# Sheet1.net
KiCad netlist of a schematic drawn in Altium Designer
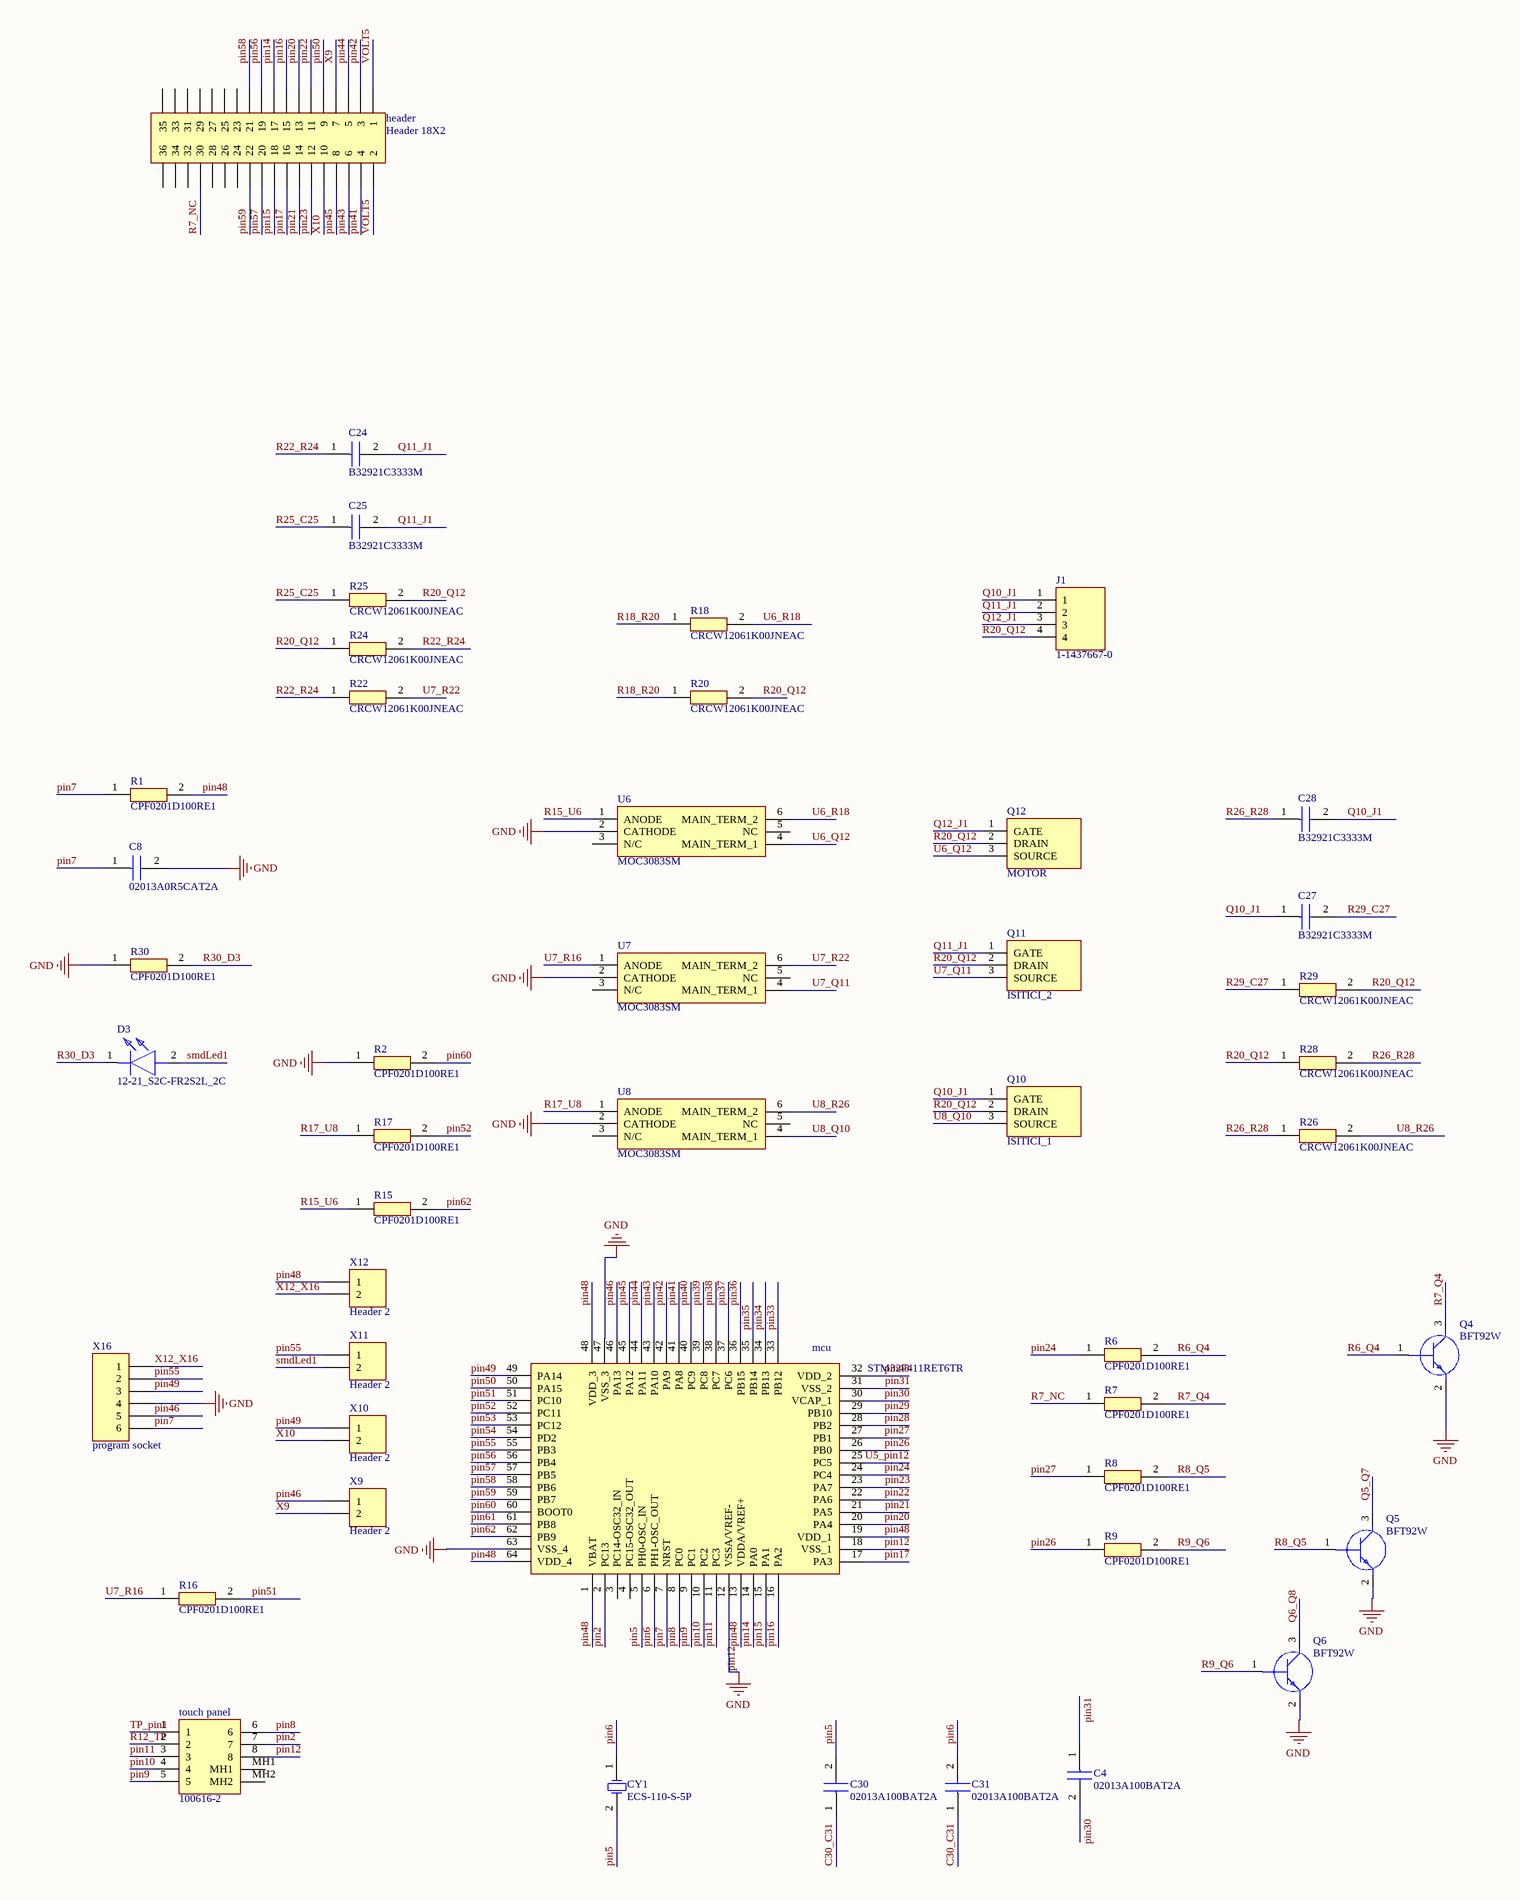
[diagram p0: Sheet1.SchDoc, left]
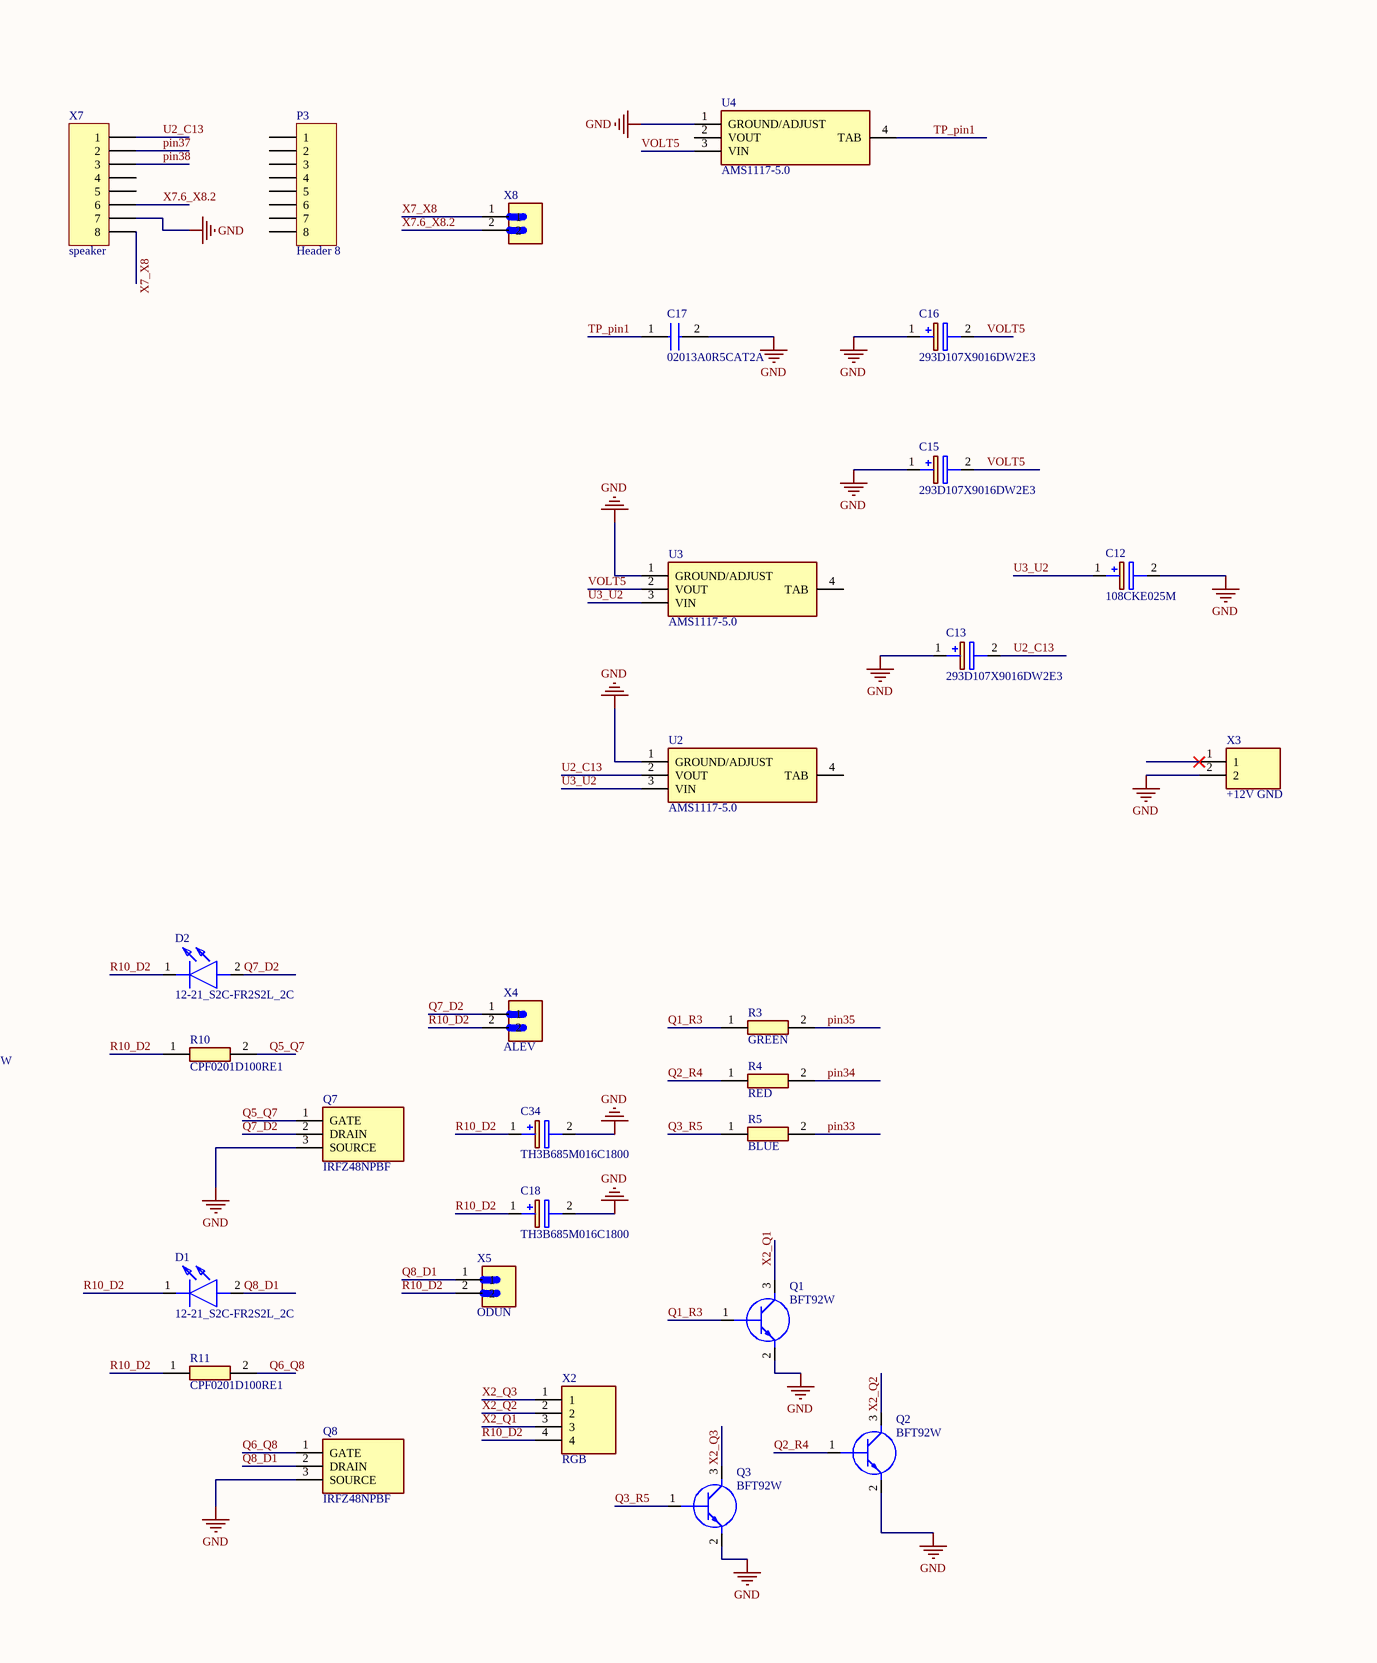
[diagram p1: Sheet1.SchDoc, middle]
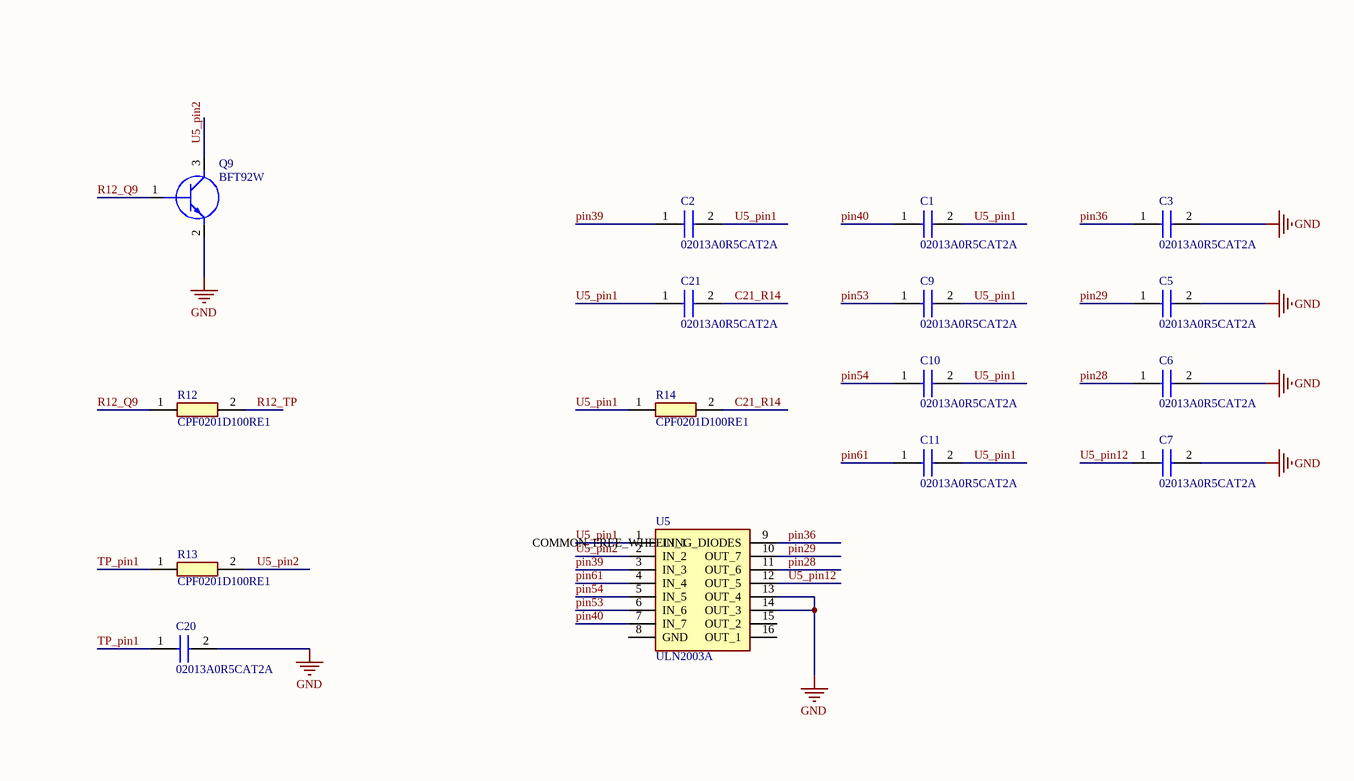
[diagram p2: Sheet1.SchDoc, right]

(export (version "E")
  (design (tool "Eeschema 10.0.6"))
  (components
    (comp (ref "C1")
      (value "02013A0R5CAT2A")
      (footprint "SamacSys:CAPC0603X33N")
      (description "Capacitor")
      (fields (field (name "MOUSER PART NUMBER") "581-02013A0R5C"))
      (libsource (lib "*") (part "02013A0R5CAT2A"))
    )
    (comp (ref "C2")
      (value "02013A0R5CAT2A")
      (footprint "SamacSys:CAPC0603X33N")
      (description "Capacitor")
      (fields (field (name "MOUSER PART NUMBER") "581-02013A0R5C"))
      (libsource (lib "*") (part "02013A0R5CAT2A"))
    )
    (comp (ref "C3")
      (value "02013A0R5CAT2A")
      (footprint "SamacSys:CAPC0603X33N")
      (description "Capacitor")
      (fields (field (name "MOUSER PART NUMBER") "581-02013A0R5C"))
      (libsource (lib "*") (part "02013A0R5CAT2A"))
    )
    (comp (ref "C4")
      (value "02013A100BAT2A")
      (footprint "SamacSys:CAPC0603X33N")
      (description "Capacitor")
      (fields (field (name "MOUSER PART NUMBER") "581-02013A100BAT2A"))
      (libsource (lib "*") (part "02013A100BAT2A"))
    )
    (comp (ref "C5")
      (value "02013A0R5CAT2A")
      (footprint "SamacSys:CAPC0603X33N")
      (description "Capacitor")
      (fields (field (name "MOUSER PART NUMBER") "581-02013A0R5C"))
      (libsource (lib "*") (part "02013A0R5CAT2A"))
    )
    (comp (ref "C6")
      (value "02013A0R5CAT2A")
      (footprint "SamacSys:CAPC0603X33N")
      (description "Capacitor")
      (fields (field (name "MOUSER PART NUMBER") "581-02013A0R5C"))
      (libsource (lib "*") (part "02013A0R5CAT2A"))
    )
    (comp (ref "C7")
      (value "02013A0R5CAT2A")
      (footprint "SamacSys:CAPC0603X33N")
      (description "Capacitor")
      (fields (field (name "MOUSER PART NUMBER") "581-02013A0R5C"))
      (libsource (lib "*") (part "02013A0R5CAT2A"))
    )
    (comp (ref "C8")
      (value "02013A0R5CAT2A")
      (footprint "SamacSys:CAPC0603X33N")
      (description "Capacitor")
      (fields (field (name "MOUSER PART NUMBER") "581-02013A0R5C"))
      (libsource (lib "*") (part "02013A0R5CAT2A"))
    )
    (comp (ref "C9")
      (value "02013A0R5CAT2A")
      (footprint "SamacSys:CAPC0603X33N")
      (description "Capacitor")
      (fields (field (name "MOUSER PART NUMBER") "581-02013A0R5C"))
      (libsource (lib "*") (part "02013A0R5CAT2A"))
    )
    (comp (ref "C10")
      (value "02013A0R5CAT2A")
      (footprint "SamacSys:CAPC0603X33N")
      (description "Capacitor")
      (fields (field (name "MOUSER PART NUMBER") "581-02013A0R5C"))
      (libsource (lib "*") (part "02013A0R5CAT2A"))
    )
    (comp (ref "C11")
      (value "02013A0R5CAT2A")
      (footprint "SamacSys:CAPC0603X33N")
      (description "Capacitor")
      (fields (field (name "MOUSER PART NUMBER") "581-02013A0R5C"))
      (libsource (lib "*") (part "02013A0R5CAT2A"))
    )
    (comp (ref "C12")
      (value "108CKE025M")
      (footprint "SamacSys:CAPPRD550W60D1050H2150")
      (description "Capacitor Polarised")
      (libsource (lib "*") (part "108CKE025M"))
    )
    (comp (ref "C13")
      (value "293D107X9016DW2E3")
      (footprint "SamacSys:CAPPM7343X310N")
      (description "Capacitor Polarised")
      (libsource (lib "*") (part "293D107X9016DW2E3"))
    )
    (comp (ref "C15")
      (value "293D107X9016DW2E3")
      (footprint "SamacSys:CAPPM7343X310N")
      (description "Capacitor Polarised")
      (libsource (lib "*") (part "293D107X9016DW2E3"))
    )
    (comp (ref "C16")
      (value "293D107X9016DW2E3")
      (footprint "SamacSys:CAPPM7343X310N")
      (description "Capacitor Polarised")
      (libsource (lib "*") (part "293D107X9016DW2E3"))
    )
    (comp (ref "C17")
      (value "02013A0R5CAT2A")
      (footprint "SamacSys:CAPC0603X33N")
      (description "Capacitor")
      (fields (field (name "MOUSER PART NUMBER") "581-02013A0R5C"))
      (libsource (lib "*") (part "02013A0R5CAT2A"))
    )
    (comp (ref "C18")
      (value "TH3B685M016C1800")
      (footprint "SamacSys:CAPPM3528X210N")
      (description "Capacitor Polarised")
      (libsource (lib "*") (part "TH3B685M016C1800"))
    )
    (comp (ref "C20")
      (value "02013A0R5CAT2A")
      (footprint "SamacSys:CAPC0603X33N")
      (description "Capacitor")
      (fields (field (name "MOUSER PART NUMBER") "581-02013A0R5C"))
      (libsource (lib "*") (part "02013A0R5CAT2A"))
    )
    (comp (ref "C21")
      (value "02013A0R5CAT2A")
      (footprint "SamacSys:CAPC0603X33N")
      (description "Capacitor")
      (fields (field (name "MOUSER PART NUMBER") "581-02013A0R5C"))
      (libsource (lib "*") (part "02013A0R5CAT2A"))
    )
    (comp (ref "C24")
      (value "B32921C3333M")
      (footprint "SamacSys:B32921C3333M")
      (description "Capacitor")
      (fields (field (name "MOUSER PART NUMBER") "871-B32921C3333M"))
      (libsource (lib "*") (part "B32921C3333M"))
    )
    (comp (ref "C25")
      (value "B32921C3333M")
      (footprint "SamacSys:B32921C3333M")
      (description "Capacitor")
      (fields (field (name "MOUSER PART NUMBER") "871-B32921C3333M"))
      (libsource (lib "*") (part "B32921C3333M"))
    )
    (comp (ref "C27")
      (value "B32921C3333M")
      (footprint "SamacSys:B32921C3333M")
      (description "Capacitor")
      (fields (field (name "MOUSER PART NUMBER") "871-B32921C3333M"))
      (libsource (lib "*") (part "B32921C3333M"))
    )
    (comp (ref "C28")
      (value "B32921C3333M")
      (footprint "SamacSys:B32921C3333M")
      (description "Capacitor")
      (fields (field (name "MOUSER PART NUMBER") "871-B32921C3333M"))
      (libsource (lib "*") (part "B32921C3333M"))
    )
    (comp (ref "C30")
      (value "02013A100BAT2A")
      (footprint "SamacSys:CAPC0603X33N")
      (description "Capacitor")
      (fields (field (name "MOUSER PART NUMBER") "581-02013A100BAT2A"))
      (libsource (lib "*") (part "02013A100BAT2A"))
    )
    (comp (ref "C31")
      (value "02013A100BAT2A")
      (footprint "SamacSys:CAPC0603X33N")
      (description "Capacitor")
      (fields (field (name "MOUSER PART NUMBER") "581-02013A100BAT2A"))
      (libsource (lib "*") (part "02013A100BAT2A"))
    )
    (comp (ref "C34")
      (value "TH3B685M016C1800")
      (footprint "SamacSys:CAPPM3528X210N")
      (description "Capacitor Polarised")
      (libsource (lib "*") (part "TH3B685M016C1800"))
    )
    (comp (ref "CY1")
      (value "ECS-110-S-5P")
      (footprint "CSM-7")
      (description "Crystal Oscillator")
      (fields (field (name "PUBLISHER") "Altium Limited"))
      (libsource (lib "ECS Crystal Oscillator") (part "ECS-110-S-5P"))
    )
    (comp (ref "D1")
      (value "12-21_S2C-FR2S2L_2C")
      (footprint "SamacSys:1221S2CFR2S2L2C")
      (description "LED")
      (fields (field (name "MANUFACTURER_PART_NUMBER") "12-21/S2C-FR2S2L/2C"))
      (libsource (lib "SamacSys") (part "12-21_S2C-FR2S2L_2C"))
    )
    (comp (ref "D2")
      (value "12-21_S2C-FR2S2L_2C")
      (footprint "SamacSys:1221S2CFR2S2L2C")
      (description "LED")
      (fields (field (name "MANUFACTURER_PART_NUMBER") "12-21/S2C-FR2S2L/2C"))
      (libsource (lib "SamacSys") (part "12-21_S2C-FR2S2L_2C"))
    )
    (comp (ref "D3")
      (value "12-21_S2C-FR2S2L_2C")
      (footprint "SamacSys:1221S2CFR2S2L2C")
      (description "LED")
      (fields (field (name "MANUFACTURER_PART_NUMBER") "12-21/S2C-FR2S2L/2C"))
      (libsource (lib "*") (part "12-21_S2C-FR2S2L_2C"))
    )
    (comp (ref "header")
      (value "Header 18X2")
      (footprint "HDR2X18")
      (description "Header, 18-Pin, Dual row")
      (fields (field (name "PUBLISHER") "Altium Limited"))
      (libsource (lib "Miscellaneous Connectors") (part "Header 18X2"))
    )
    (comp (ref "J1")
      (value "1-1437667-0")
      (footprint "SamacSys:114376670")
      (description "Connector")
      (libsource (lib "*") (part "1-1437667-0"))
    )
    (comp (ref "mcu")
      (value "STM32F411RET6TR")
      (footprint "SamacSys:QFP50P1200X1200X160-64N")
      (description "Integrated Circuit")
      (fields (field (name "MOUSER PART NUMBER") "511-STM32F411RET6TR"))
      (libsource (lib "*") (part "STM32F411RET6TR"))
    )
    (comp (ref "P3")
      (value "Header 8")
      (footprint "HDR1X8")
      (description "Header, 8-Pin")
      (fields (field (name "PUBLISHER") "Altium Limited"))
      (libsource (lib "") (part "Header 8_1"))
    )
    (comp (ref "Q1")
      (value "BFT92W")
      (footprint "SamacSys:SOT65P210X110-3N")
      (description "Transistor BJT NPN")
      (libsource (lib "*") (part "BFT92W"))
    )
    (comp (ref "Q2")
      (value "BFT92W")
      (footprint "SamacSys:SOT65P210X110-3N")
      (description "Transistor BJT NPN")
      (libsource (lib "*") (part "BFT92W"))
    )
    (comp (ref "Q3")
      (value "BFT92W")
      (footprint "SamacSys:SOT65P210X110-3N")
      (description "Transistor BJT NPN")
      (libsource (lib "*") (part "BFT92W"))
    )
    (comp (ref "Q4")
      (value "BFT92W")
      (footprint "SamacSys:SOT65P210X110-3N")
      (description "Transistor BJT NPN")
      (libsource (lib "*") (part "BFT92W"))
    )
    (comp (ref "Q5")
      (value "BFT92W")
      (footprint "SamacSys:SOT65P210X110-3N")
      (description "Transistor BJT NPN")
      (libsource (lib "*") (part "BFT92W"))
    )
    (comp (ref "Q6")
      (value "BFT92W")
      (footprint "SamacSys:SOT65P210X110-3N")
      (description "Transistor BJT NPN")
      (libsource (lib "*") (part "BFT92W"))
    )
    (comp (ref "Q7")
      (value "IRFZ48NPBF")
      (footprint "SamacSys:TO254P483X1016X1994-3P")
      (description "Transistor")
      (fields (field (name "MOUSER PART NUMBER") "942-IRFZ48NPBF"))
      (libsource (lib "SamacSys") (part "IRFZ48NPBF"))
    )
    (comp (ref "Q8")
      (value "IRFZ48NPBF")
      (footprint "SamacSys:TO254P483X1016X1994-3P")
      (description "Transistor")
      (fields (field (name "MOUSER PART NUMBER") "942-IRFZ48NPBF"))
      (libsource (lib "SamacSys") (part "IRFZ48NPBF"))
    )
    (comp (ref "Q9")
      (value "BFT92W")
      (footprint "SamacSys:SOT65P210X110-3N")
      (description "Transistor BJT NPN")
      (libsource (lib "*") (part "BFT92W"))
    )
    (comp (ref "Q10")
      (value "ISITICI_1")
      (footprint "SamacSys:TO254P483X1016X1994-3P")
      (description "Transistor")
      (fields
        (field (name "MANUFACTURER_PART_NUMBER") "IRFZ48NPBF")
        (field (name "MOUSER PART NUMBER") "942-IRFZ48NPBF")
      )
      (libsource (lib "SamacSys") (part "IRFZ48NPBF"))
    )
    (comp (ref "Q11")
      (value "ISITICI_2")
      (footprint "SamacSys:TO254P483X1016X1994-3P")
      (description "Transistor")
      (fields
        (field (name "MANUFACTURER_PART_NUMBER") "IRFZ48NPBF")
        (field (name "MOUSER PART NUMBER") "942-IRFZ48NPBF")
      )
      (libsource (lib "SamacSys") (part "IRFZ48NPBF"))
    )
    (comp (ref "Q12")
      (value "MOTOR")
      (footprint "SamacSys:TO254P483X1016X1994-3P")
      (description "Transistor")
      (fields
        (field (name "MANUFACTURER_PART_NUMBER") "IRFZ48NPBF")
        (field (name "MOUSER PART NUMBER") "942-IRFZ48NPBF")
      )
      (libsource (lib "SamacSys") (part "IRFZ48NPBF"))
    )
    (comp (ref "R1")
      (value "CPF0201D100RE1")
      (footprint "SamacSys:RESC0603X28N")
      (description "Resistor")
      (fields (field (name "MOUSER PART NUMBER") "279-CPF0201D100RE1"))
      (libsource (lib "*") (part "CPF0201D100RE1"))
    )
    (comp (ref "R2")
      (value "CPF0201D100RE1")
      (footprint "SamacSys:RESC0603X28N")
      (description "Resistor")
      (fields (field (name "MOUSER PART NUMBER") "279-CPF0201D100RE1"))
      (libsource (lib "*") (part "CPF0201D100RE1"))
    )
    (comp (ref "R3")
      (value "GREEN")
      (footprint "SamacSys:RESC0603X28N")
      (description "Resistor")
      (fields
        (field (name "MANUFACTURER_PART_NUMBER") "CPF0201D100RE1")
        (field (name "MOUSER PART NUMBER") "279-CPF0201D100RE1")
      )
      (libsource (lib "*") (part "CPF0201D100RE1"))
    )
    (comp (ref "R4")
      (value "RED")
      (footprint "SamacSys:RESC0603X28N")
      (description "Resistor")
      (fields
        (field (name "MANUFACTURER_PART_NUMBER") "CPF0201D100RE1")
        (field (name "MOUSER PART NUMBER") "279-CPF0201D100RE1")
      )
      (libsource (lib "*") (part "CPF0201D100RE1"))
    )
    (comp (ref "R5")
      (value "BLUE")
      (footprint "SamacSys:RESC0603X28N")
      (description "Resistor")
      (fields
        (field (name "MANUFACTURER_PART_NUMBER") "CPF0201D100RE1")
        (field (name "MOUSER PART NUMBER") "279-CPF0201D100RE1")
      )
      (libsource (lib "*") (part "CPF0201D100RE1"))
    )
    (comp (ref "R6")
      (value "CPF0201D100RE1")
      (footprint "SamacSys:RESC0603X28N")
      (description "Resistor")
      (fields (field (name "MOUSER PART NUMBER") "279-CPF0201D100RE1"))
      (libsource (lib "*") (part "CPF0201D100RE1"))
    )
    (comp (ref "R7")
      (value "CPF0201D100RE1")
      (footprint "SamacSys:RESC0603X28N")
      (description "Resistor")
      (fields (field (name "MOUSER PART NUMBER") "279-CPF0201D100RE1"))
      (libsource (lib "*") (part "CPF0201D100RE1"))
    )
    (comp (ref "R8")
      (value "CPF0201D100RE1")
      (footprint "SamacSys:RESC0603X28N")
      (description "Resistor")
      (fields (field (name "MOUSER PART NUMBER") "279-CPF0201D100RE1"))
      (libsource (lib "*") (part "CPF0201D100RE1"))
    )
    (comp (ref "R9")
      (value "CPF0201D100RE1")
      (footprint "SamacSys:RESC0603X28N")
      (description "Resistor")
      (fields (field (name "MOUSER PART NUMBER") "279-CPF0201D100RE1"))
      (libsource (lib "*") (part "CPF0201D100RE1"))
    )
    (comp (ref "R10")
      (value "CPF0201D100RE1")
      (footprint "SamacSys:RESC0603X28N")
      (description "Resistor")
      (fields (field (name "MOUSER PART NUMBER") "279-CPF0201D100RE1"))
      (libsource (lib "*") (part "CPF0201D100RE1"))
    )
    (comp (ref "R11")
      (value "CPF0201D100RE1")
      (footprint "SamacSys:RESC0603X28N")
      (description "Resistor")
      (fields (field (name "MOUSER PART NUMBER") "279-CPF0201D100RE1"))
      (libsource (lib "*") (part "CPF0201D100RE1"))
    )
    (comp (ref "R12")
      (value "CPF0201D100RE1")
      (footprint "SamacSys:RESC0603X28N")
      (description "Resistor")
      (fields (field (name "MOUSER PART NUMBER") "279-CPF0201D100RE1"))
      (libsource (lib "*") (part "CPF0201D100RE1"))
    )
    (comp (ref "R13")
      (value "CPF0201D100RE1")
      (footprint "SamacSys:RESC0603X28N")
      (description "Resistor")
      (fields (field (name "MOUSER PART NUMBER") "279-CPF0201D100RE1"))
      (libsource (lib "*") (part "CPF0201D100RE1"))
    )
    (comp (ref "R14")
      (value "CPF0201D100RE1")
      (footprint "SamacSys:RESC0603X28N")
      (description "Resistor")
      (fields (field (name "MOUSER PART NUMBER") "279-CPF0201D100RE1"))
      (libsource (lib "*") (part "CPF0201D100RE1"))
    )
    (comp (ref "R15")
      (value "CPF0201D100RE1")
      (footprint "SamacSys:RESC0603X28N")
      (description "Resistor")
      (fields (field (name "MOUSER PART NUMBER") "279-CPF0201D100RE1"))
      (libsource (lib "*") (part "CPF0201D100RE1"))
    )
    (comp (ref "R16")
      (value "CPF0201D100RE1")
      (footprint "SamacSys:RESC0603X28N")
      (description "Resistor")
      (fields (field (name "MOUSER PART NUMBER") "279-CPF0201D100RE1"))
      (libsource (lib "*") (part "CPF0201D100RE1"))
    )
    (comp (ref "R17")
      (value "CPF0201D100RE1")
      (footprint "SamacSys:RESC0603X28N")
      (description "Resistor")
      (fields (field (name "MOUSER PART NUMBER") "279-CPF0201D100RE1"))
      (libsource (lib "*") (part "CPF0201D100RE1"))
    )
    (comp (ref "R18")
      (value "CRCW12061K00JNEAC")
      (footprint "SamacSys:RESC3216X60N")
      (description "Resistor")
      (fields (field (name "MOUSER PART NUMBER") "71-CRCW12061K00JNEAC"))
      (libsource (lib "*") (part "CRCW12061K00JNEAC"))
    )
    (comp (ref "R20")
      (value "CRCW12061K00JNEAC")
      (footprint "SamacSys:RESC3216X60N")
      (description "Resistor")
      (fields (field (name "MOUSER PART NUMBER") "71-CRCW12061K00JNEAC"))
      (libsource (lib "*") (part "CRCW12061K00JNEAC"))
    )
    (comp (ref "R22")
      (value "CRCW12061K00JNEAC")
      (footprint "SamacSys:RESC3216X60N")
      (description "Resistor")
      (fields (field (name "MOUSER PART NUMBER") "71-CRCW12061K00JNEAC"))
      (libsource (lib "*") (part "CRCW12061K00JNEAC"))
    )
    (comp (ref "R24")
      (value "CRCW12061K00JNEAC")
      (footprint "SamacSys:RESC3216X60N")
      (description "Resistor")
      (fields (field (name "MOUSER PART NUMBER") "71-CRCW12061K00JNEAC"))
      (libsource (lib "*") (part "CRCW12061K00JNEAC"))
    )
    (comp (ref "R25")
      (value "CRCW12061K00JNEAC")
      (footprint "SamacSys:RESC3216X60N")
      (description "Resistor")
      (fields (field (name "MOUSER PART NUMBER") "71-CRCW12061K00JNEAC"))
      (libsource (lib "*") (part "CRCW12061K00JNEAC"))
    )
    (comp (ref "R26")
      (value "CRCW12061K00JNEAC")
      (footprint "SamacSys:RESC3216X60N")
      (description "Resistor")
      (fields (field (name "MOUSER PART NUMBER") "71-CRCW12061K00JNEAC"))
      (libsource (lib "*") (part "CRCW12061K00JNEAC"))
    )
    (comp (ref "R28")
      (value "CRCW12061K00JNEAC")
      (footprint "SamacSys:RESC3216X60N")
      (description "Resistor")
      (fields (field (name "MOUSER PART NUMBER") "71-CRCW12061K00JNEAC"))
      (libsource (lib "*") (part "CRCW12061K00JNEAC"))
    )
    (comp (ref "R29")
      (value "CRCW12061K00JNEAC")
      (footprint "SamacSys:RESC3216X60N")
      (description "Resistor")
      (fields (field (name "MOUSER PART NUMBER") "71-CRCW12061K00JNEAC"))
      (libsource (lib "*") (part "CRCW12061K00JNEAC"))
    )
    (comp (ref "R30")
      (value "CPF0201D100RE1")
      (footprint "SamacSys:RESC0603X28N")
      (description "Resistor")
      (fields (field (name "MOUSER PART NUMBER") "279-CPF0201D100RE1"))
      (libsource (lib "*") (part "CPF0201D100RE1"))
    )
    (comp (ref "touch panel")
      (value "100616-2")
      (footprint "SamacSys:1006162")
      (description "Connector")
      (fields (field (name "MOUSER PART NUMBER") "571-100616-2"))
      (libsource (lib "SamacSys") (part "100616-2"))
    )
    (comp (ref "U2")
      (value "AMS1117-5.0")
      (footprint "SamacSys:SOT229P700X180-4N")
      (description "Integrated Circuit")
      (libsource (lib "*") (part "AMS1117-5.0"))
    )
    (comp (ref "U3")
      (value "AMS1117-5.0")
      (footprint "SamacSys:SOT229P700X180-4N")
      (description "Integrated Circuit")
      (libsource (lib "*") (part "AMS1117-5.0"))
    )
    (comp (ref "U4")
      (value "AMS1117-5.0")
      (footprint "SamacSys:SOT229P700X180-4N")
      (description "Integrated Circuit")
      (libsource (lib "*") (part "AMS1117-5.0"))
    )
    (comp (ref "U5")
      (value "ULN2003A")
      (footprint "SamacSys:DIP794W56P254L1888H533Q16N")
      (description "Integrated Circuit")
      (fields (field (name "MOUSER PART NUMBER") "511-ULN2003A"))
      (libsource (lib "*") (part "ULN2003A"))
    )
    (comp (ref "U6")
      (value "MOC3083SM")
      (footprint "SamacSys:DIP762W51P254L851H508Q6N")
      (description "Integrated Circuit")
      (fields (field (name "MOUSER PART NUMBER") "512-MOC3083SM"))
      (libsource (lib "*") (part "MOC3083SM"))
    )
    (comp (ref "U7")
      (value "MOC3083SM")
      (footprint "SamacSys:DIP762W51P254L851H508Q6N")
      (description "Integrated Circuit")
      (fields (field (name "MOUSER PART NUMBER") "512-MOC3083SM"))
      (libsource (lib "*") (part "MOC3083SM"))
    )
    (comp (ref "U8")
      (value "MOC3083SM")
      (footprint "SamacSys:DIP762W51P254L851H508Q6N")
      (description "Integrated Circuit")
      (fields (field (name "MOUSER PART NUMBER") "512-MOC3083SM"))
      (libsource (lib "*") (part "MOC3083SM"))
    )
    (comp (ref "X2")
      (value "RGB")
      (footprint "SamacSys:1844236")
      (description "Connector")
      (fields
        (field (name "MANUFACTURER_PART_NUMBER") "1844236")
        (field (name "MOUSER PART NUMBER") "651-1844236")
      )
      (libsource (lib "*") (part "1844236"))
    )
    (comp (ref "X3")
      (value "+12V GND")
      (footprint "SamacSys:SHDR2W100P0X508_1X2_1020X780X1200P")
      (description "Connector")
      (fields (field (name "MANUFACTURER_PART_NUMBER") "CTBP9308/2AO"))
      (libsource (lib "*") (part "CTBP9308_2AO"))
    )
    (comp (ref "X4")
      (value "ALEV")
      (footprint "PHOENIX_1803277")
      (fields
        (field (name "DIGI-KEY_PART_NUMBER") "277-1206-ND")
        (field (name "MP") "1803277")
        (field (name "MF") "Phoenix Contact")
      )
      (libsource (lib "1803277") (part "1803277"))
    )
    (comp (ref "X5")
      (value "ODUN")
      (footprint "PHOENIX_1803277")
      (fields
        (field (name "DIGI-KEY_PART_NUMBER") "277-1206-ND")
        (field (name "MP") "1803277")
        (field (name "MF") "Phoenix Contact")
      )
      (libsource (lib "1803277") (part "1803277"))
    )
    (comp (ref "X7")
      (value "speaker")
      (footprint "HDR1X8")
      (description "Header, 8-Pin")
      (fields (field (name "PUBLISHER") "Altium Limited"))
      (libsource (lib "Miscellaneous Connectors") (part "Header 8"))
    )
    (comp (ref "X8")
      (value "~")
      (footprint "PHOENIX_1803277")
      (fields
        (field (name "DIGI-KEY_PART_NUMBER") "277-1206-ND")
        (field (name "MP") "1803277")
        (field (name "MF") "Phoenix Contact")
      )
      (libsource (lib "1803277") (part "1803277"))
    )
    (comp (ref "X9")
      (value "Header 2")
      (footprint "HDR1X2")
      (description "Header, 2-Pin")
      (fields (field (name "PUBLISHER") "Altium Limited"))
      (libsource (lib "Miscellaneous Connectors") (part "Header 2"))
    )
    (comp (ref "X10")
      (value "Header 2")
      (footprint "HDR1X2")
      (description "Header, 2-Pin")
      (fields (field (name "PUBLISHER") "Altium Limited"))
      (libsource (lib "Miscellaneous Connectors") (part "Header 2"))
    )
    (comp (ref "X11")
      (value "Header 2")
      (footprint "HDR1X2")
      (description "Header, 2-Pin")
      (fields (field (name "PUBLISHER") "Altium Limited"))
      (libsource (lib "Miscellaneous Connectors") (part "Header 2"))
    )
    (comp (ref "X12")
      (value "Header 2")
      (footprint "HDR1X2")
      (description "Header, 2-Pin")
      (fields (field (name "PUBLISHER") "Altium Limited"))
      (libsource (lib "Miscellaneous Connectors") (part "Header 2"))
    )
    (comp (ref "X16")
      (value "program socket")
      (footprint "HDR1X6")
      (description "Header, 6-Pin")
      (fields (field (name "PUBLISHER") "Altium Limited"))
      (libsource (lib "Miscellaneous Connectors") (part "Header 6"))
    )
  )
  (nets
    (net (code "1") (name "/C21_R14") (class "Default")
      (node (ref "C21") (pin "2") (pinfunction "2_2") (pintype "passive"))
      (node (ref "R14") (pin "2") (pinfunction "2_2") (pintype "passive"))
    )
    (net (code "2") (name "/C30_C31") (class "Default")
      (node (ref "C30") (pin "1") (pinfunction "1_1") (pintype "passive"))
      (node (ref "C31") (pin "1") (pinfunction "1_1") (pintype "passive"))
    )
    (net (code "3") (name "/Q1_R3") (class "Default")
      (node (ref "Q1") (pin "1") (pinfunction "B_1") (pintype "passive"))
      (node (ref "R3") (pin "1") (pinfunction "1_1") (pintype "passive"))
    )
    (net (code "4") (name "/Q2_R4") (class "Default")
      (node (ref "Q2") (pin "1") (pinfunction "B_1") (pintype "passive"))
      (node (ref "R4") (pin "1") (pinfunction "1_1") (pintype "passive"))
    )
    (net (code "5") (name "/Q3_R5") (class "Default")
      (node (ref "Q3") (pin "1") (pinfunction "B_1") (pintype "passive"))
      (node (ref "R5") (pin "1") (pinfunction "1_1") (pintype "passive"))
    )
    (net (code "6") (name "/Q5_Q7") (class "Default")
      (node (ref "Q5") (pin "3") (pinfunction "C_3") (pintype "passive"))
      (node (ref "Q7") (pin "1") (pinfunction "GATE_1") (pintype "passive"))
      (node (ref "R10") (pin "2") (pinfunction "2_2") (pintype "passive"))
    )
    (net (code "7") (name "/Q6_Q8") (class "Default")
      (node (ref "Q6") (pin "3") (pinfunction "C_3") (pintype "passive"))
      (node (ref "Q8") (pin "1") (pinfunction "GATE_1") (pintype "passive"))
      (node (ref "R11") (pin "2") (pinfunction "2_2") (pintype "passive"))
    )
    (net (code "8") (name "/Q7_D2") (class "Default")
      (node (ref "D2") (pin "2") (pinfunction "A_2") (pintype "passive"))
      (node (ref "Q7") (pin "2") (pinfunction "DRAIN_2") (pintype "passive"))
      (node (ref "X4") (pin "1") (pinfunction "1_1") (pintype "passive"))
    )
    (net (code "9") (name "/Q8_D1") (class "Default")
      (node (ref "D1") (pin "2") (pinfunction "A_2") (pintype "passive"))
      (node (ref "Q8") (pin "2") (pinfunction "DRAIN_2") (pintype "passive"))
      (node (ref "X5") (pin "1") (pinfunction "1_1") (pintype "passive"))
    )
    (net (code "10") (name "/Q10_J1") (class "Default")
      (node (ref "C27") (pin "1") (pinfunction "1_1") (pintype "passive"))
      (node (ref "C28") (pin "2") (pinfunction "2_2") (pintype "passive"))
      (node (ref "J1") (pin "1") (pinfunction "1_1") (pintype "passive"))
      (node (ref "Q10") (pin "1") (pinfunction "GATE_1") (pintype "passive"))
    )
    (net (code "11") (name "/Q11_J1") (class "Default")
      (node (ref "C24") (pin "2") (pinfunction "2_2") (pintype "passive"))
      (node (ref "C25") (pin "2") (pinfunction "2_2") (pintype "passive"))
      (node (ref "J1") (pin "2") (pinfunction "2_2") (pintype "passive"))
      (node (ref "Q11") (pin "1") (pinfunction "GATE_1") (pintype "passive"))
    )
    (net (code "12") (name "/Q12_J1") (class "Default")
      (node (ref "J1") (pin "3") (pinfunction "3_3") (pintype "passive"))
      (node (ref "Q12") (pin "1") (pinfunction "GATE_1") (pintype "passive"))
    )
    (net (code "13") (name "/R6_Q4") (class "Default")
      (node (ref "Q4") (pin "1") (pinfunction "B_1") (pintype "passive"))
      (node (ref "R6") (pin "2") (pinfunction "2_2") (pintype "passive"))
    )
    (net (code "14") (name "/R7_NC") (class "Default")
      (node (ref "R7") (pin "1") (pinfunction "1_1") (pintype "passive"))
      (node (ref "header") (pin "30") (pinfunction "30_30") (pintype "passive"))
    )
    (net (code "15") (name "/R7_Q4") (class "Default")
      (node (ref "Q4") (pin "3") (pinfunction "C_3") (pintype "passive"))
      (node (ref "R7") (pin "2") (pinfunction "2_2") (pintype "passive"))
    )
    (net (code "16") (name "/R8_Q5") (class "Default")
      (node (ref "Q5") (pin "1") (pinfunction "B_1") (pintype "passive"))
      (node (ref "R8") (pin "2") (pinfunction "2_2") (pintype "passive"))
    )
    (net (code "17") (name "/R9_Q6") (class "Default")
      (node (ref "Q6") (pin "1") (pinfunction "B_1") (pintype "passive"))
      (node (ref "R9") (pin "2") (pinfunction "2_2") (pintype "passive"))
    )
    (net (code "18") (name "/R10_D2") (class "Default")
      (node (ref "C18") (pin "1") (pinfunction "+_1") (pintype "passive"))
      (node (ref "C34") (pin "1") (pinfunction "+_1") (pintype "passive"))
      (node (ref "D1") (pin "1") (pinfunction "K_1") (pintype "passive"))
      (node (ref "D2") (pin "1") (pinfunction "K_1") (pintype "passive"))
      (node (ref "R10") (pin "1") (pinfunction "1_1") (pintype "passive"))
      (node (ref "R11") (pin "1") (pinfunction "1_1") (pintype "passive"))
      (node (ref "X2") (pin "4") (pinfunction "4_4") (pintype "passive"))
      (node (ref "X4") (pin "2") (pinfunction "2_2") (pintype "passive"))
      (node (ref "X5") (pin "2") (pinfunction "2_2") (pintype "passive"))
    )
    (net (code "19") (name "/R12_Q9") (class "Default")
      (node (ref "Q9") (pin "1") (pinfunction "B_1") (pintype "passive"))
      (node (ref "R12") (pin "1") (pinfunction "1_1") (pintype "passive"))
    )
    (net (code "20") (name "/R12_TP") (class "Default")
      (node (ref "R12") (pin "2") (pinfunction "2_2") (pintype "passive"))
      (node (ref "touch panel") (pin "2") (pinfunction "2_2") (pintype "passive"))
    )
    (net (code "21") (name "/R15_U6") (class "Default")
      (node (ref "R15") (pin "1") (pinfunction "1_1") (pintype "passive"))
      (node (ref "U6") (pin "1") (pinfunction "ANODE_1") (pintype "passive"))
    )
    (net (code "22") (name "/R17_U8") (class "Default")
      (node (ref "R17") (pin "1") (pinfunction "1_1") (pintype "passive"))
      (node (ref "U8") (pin "1") (pinfunction "ANODE_1") (pintype "passive"))
    )
    (net (code "23") (name "/R18_R20") (class "Default")
      (node (ref "R18") (pin "1") (pinfunction "1_1") (pintype "passive"))
      (node (ref "R20") (pin "1") (pinfunction "1_1") (pintype "passive"))
    )
    (net (code "24") (name "/R20_Q12") (class "Default")
      (node (ref "J1") (pin "4") (pinfunction "4_4") (pintype "passive"))
      (node (ref "Q10") (pin "2") (pinfunction "DRAIN_2") (pintype "passive"))
      (node (ref "Q11") (pin "2") (pinfunction "DRAIN_2") (pintype "passive"))
      (node (ref "Q12") (pin "2") (pinfunction "DRAIN_2") (pintype "passive"))
      (node (ref "R20") (pin "2") (pinfunction "2_2") (pintype "passive"))
      (node (ref "R24") (pin "1") (pinfunction "1_1") (pintype "passive"))
      (node (ref "R25") (pin "2") (pinfunction "2_2") (pintype "passive"))
      (node (ref "R28") (pin "1") (pinfunction "1_1") (pintype "passive"))
      (node (ref "R29") (pin "2") (pinfunction "2_2") (pintype "passive"))
    )
    (net (code "25") (name "/R22_R24") (class "Default")
      (node (ref "C24") (pin "1") (pinfunction "1_1") (pintype "passive"))
      (node (ref "R22") (pin "1") (pinfunction "1_1") (pintype "passive"))
      (node (ref "R24") (pin "2") (pinfunction "2_2") (pintype "passive"))
    )
    (net (code "26") (name "/R25_C25") (class "Default")
      (node (ref "C25") (pin "1") (pinfunction "1_1") (pintype "passive"))
      (node (ref "R25") (pin "1") (pinfunction "1_1") (pintype "passive"))
    )
    (net (code "27") (name "/R26_R28") (class "Default")
      (node (ref "C28") (pin "1") (pinfunction "1_1") (pintype "passive"))
      (node (ref "R26") (pin "1") (pinfunction "1_1") (pintype "passive"))
      (node (ref "R28") (pin "2") (pinfunction "2_2") (pintype "passive"))
    )
    (net (code "28") (name "/R29_C27") (class "Default")
      (node (ref "C27") (pin "2") (pinfunction "2_2") (pintype "passive"))
      (node (ref "R29") (pin "1") (pinfunction "1_1") (pintype "passive"))
    )
    (net (code "29") (name "/R30_D3") (class "Default")
      (node (ref "D3") (pin "1") (pinfunction "K_1") (pintype "passive"))
      (node (ref "R30") (pin "2") (pinfunction "2_2") (pintype "passive"))
    )
    (net (code "30") (name "/TP_pin1") (class "Default")
      (node (ref "C17") (pin "1") (pinfunction "1_1") (pintype "passive"))
      (node (ref "C20") (pin "1") (pinfunction "1_1") (pintype "passive"))
      (node (ref "R13") (pin "1") (pinfunction "1_1") (pintype "passive"))
      (node (ref "U4") (pin "4") (pinfunction "TAB_4") (pintype "passive"))
      (node (ref "touch panel") (pin "1") (pinfunction "1_1") (pintype "passive"))
    )
    (net (code "31") (name "/U2_C13") (class "Default")
      (node (ref "C13") (pin "2") (pinfunction "-_2") (pintype "passive"))
      (node (ref "U2") (pin "2") (pinfunction "VOUT_2") (pintype "passive"))
      (node (ref "X7") (pin "1") (pinfunction "1_1") (pintype "passive"))
    )
    (net (code "32") (name "/U3_U2") (class "Default")
      (node (ref "C12") (pin "1") (pinfunction "+_1") (pintype "passive"))
      (node (ref "U2") (pin "3") (pinfunction "VIN_3") (pintype "passive"))
      (node (ref "U3") (pin "3") (pinfunction "VIN_3") (pintype "passive"))
    )
    (net (code "33") (name "/U5_pin1") (class "Default")
      (node (ref "C1") (pin "2") (pinfunction "2_2") (pintype "passive"))
      (node (ref "C10") (pin "2") (pinfunction "2_2") (pintype "passive"))
      (node (ref "C11") (pin "2") (pinfunction "2_2") (pintype "passive"))
      (node (ref "C2") (pin "2") (pinfunction "2_2") (pintype "passive"))
      (node (ref "C21") (pin "1") (pinfunction "1_1") (pintype "passive"))
      (node (ref "C9") (pin "2") (pinfunction "2_2") (pintype "passive"))
      (node (ref "R14") (pin "1") (pinfunction "1_1") (pintype "passive"))
      (node (ref "U5") (pin "1") (pinfunction "IN_1_1") (pintype "passive"))
    )
    (net (code "34") (name "/U5_pin2") (class "Default")
      (node (ref "Q9") (pin "3") (pinfunction "C_3") (pintype "passive"))
      (node (ref "R13") (pin "2") (pinfunction "2_2") (pintype "passive"))
      (node (ref "U5") (pin "2") (pinfunction "IN_2_2") (pintype "passive"))
    )
    (net (code "35") (name "/U5_pin12") (class "Default")
      (node (ref "C7") (pin "1") (pinfunction "1_1") (pintype "passive"))
      (node (ref "U5") (pin "12") (pinfunction "OUT_5_12") (pintype "passive"))
      (node (ref "mcu") (pin "25") (pinfunction "PC5_25") (pintype "passive"))
    )
    (net (code "36") (name "/U6_Q12") (class "Default")
      (node (ref "Q12") (pin "3") (pinfunction "SOURCE_3") (pintype "passive"))
      (node (ref "U6") (pin "4") (pinfunction "MAIN_TERM_1_4") (pintype "passive"))
    )
    (net (code "37") (name "/U6_R18") (class "Default")
      (node (ref "R18") (pin "2") (pinfunction "2_2") (pintype "passive"))
      (node (ref "U6") (pin "6") (pinfunction "MAIN_TERM_2_6") (pintype "passive"))
    )
    (net (code "38") (name "/U7_Q11") (class "Default")
      (node (ref "Q11") (pin "3") (pinfunction "SOURCE_3") (pintype "passive"))
      (node (ref "U7") (pin "4") (pinfunction "MAIN_TERM_1_4") (pintype "passive"))
    )
    (net (code "39") (name "/U7_R16") (class "Default")
      (node (ref "R16") (pin "1") (pinfunction "1_1") (pintype "passive"))
      (node (ref "U7") (pin "1") (pinfunction "ANODE_1") (pintype "passive"))
    )
    (net (code "40") (name "/U7_R22") (class "Default")
      (node (ref "R22") (pin "2") (pinfunction "2_2") (pintype "passive"))
      (node (ref "U7") (pin "6") (pinfunction "MAIN_TERM_2_6") (pintype "passive"))
    )
    (net (code "41") (name "/U8_Q10") (class "Default")
      (node (ref "Q10") (pin "3") (pinfunction "SOURCE_3") (pintype "passive"))
      (node (ref "U8") (pin "4") (pinfunction "MAIN_TERM_1_4") (pintype "passive"))
    )
    (net (code "42") (name "/U8_R26") (class "Default")
      (node (ref "R26") (pin "2") (pinfunction "2_2") (pintype "passive"))
      (node (ref "U8") (pin "6") (pinfunction "MAIN_TERM_2_6") (pintype "passive"))
    )
    (net (code "43") (name "/VOLT5") (class "Default")
      (node (ref "C15") (pin "2") (pinfunction "-_2") (pintype "passive"))
      (node (ref "C16") (pin "2") (pinfunction "-_2") (pintype "passive"))
      (node (ref "U3") (pin "2") (pinfunction "VOUT_2") (pintype "passive"))
      (node (ref "U4") (pin "3") (pinfunction "VIN_3") (pintype "passive"))
      (node (ref "header") (pin "1") (pinfunction "1_1") (pintype "passive"))
      (node (ref "header") (pin "2") (pinfunction "2_2") (pintype "passive"))
    )
    (net (code "44") (name "/X2_Q1") (class "Default")
      (node (ref "Q1") (pin "3") (pinfunction "C_3") (pintype "passive"))
      (node (ref "X2") (pin "3") (pinfunction "3_3") (pintype "passive"))
    )
    (net (code "45") (name "/X2_Q2") (class "Default")
      (node (ref "Q2") (pin "3") (pinfunction "C_3") (pintype "passive"))
      (node (ref "X2") (pin "2") (pinfunction "2_2") (pintype "passive"))
    )
    (net (code "46") (name "/X2_Q3") (class "Default")
      (node (ref "Q3") (pin "3") (pinfunction "C_3") (pintype "passive"))
      (node (ref "X2") (pin "1") (pinfunction "1_1") (pintype "passive"))
    )
    (net (code "47") (name "/X7.6_X8.2") (class "Default")
      (node (ref "X7") (pin "6") (pinfunction "6_6") (pintype "passive"))
      (node (ref "X8") (pin "2") (pinfunction "2_2") (pintype "passive"))
    )
    (net (code "48") (name "/X7_X8") (class "Default")
      (node (ref "X7") (pin "8") (pinfunction "8_8") (pintype "passive"))
      (node (ref "X8") (pin "1") (pinfunction "1_1") (pintype "passive"))
    )
    (net (code "49") (name "/X9") (class "Default")
      (node (ref "X9") (pin "2") (pinfunction "2_2") (pintype "passive"))
      (node (ref "header") (pin "7") (pinfunction "7_7") (pintype "passive"))
    )
    (net (code "50") (name "/X10") (class "Default")
      (node (ref "X10") (pin "2") (pinfunction "2_2") (pintype "passive"))
      (node (ref "header") (pin "10") (pinfunction "10_10") (pintype "passive"))
    )
    (net (code "51") (name "/X12_X16") (class "Default")
      (node (ref "X12") (pin "2") (pinfunction "2_2") (pintype "passive"))
      (node (ref "X16") (pin "1") (pinfunction "1_1") (pintype "passive"))
    )
    (net (code "52") (name "/pin2") (class "Default")
      (node (ref "mcu") (pin "2") (pinfunction "PC13_2") (pintype "passive"))
      (node (ref "touch panel") (pin "7") (pinfunction "7_7") (pintype "passive"))
    )
    (net (code "53") (name "/pin5") (class "Default")
      (node (ref "C30") (pin "2") (pinfunction "2_2") (pintype "passive"))
      (node (ref "CY1") (pin "2") (pinfunction "OSC2_2") (pintype "passive"))
      (node (ref "mcu") (pin "5") (pinfunction "PH0-OSC_IN_5") (pintype "passive"))
    )
    (net (code "54") (name "/pin6") (class "Default")
      (node (ref "C31") (pin "2") (pinfunction "2_2") (pintype "passive"))
      (node (ref "CY1") (pin "1") (pinfunction "OSC1_1") (pintype "passive"))
      (node (ref "mcu") (pin "6") (pinfunction "PH1-OSC_OUT_6") (pintype "passive"))
    )
    (net (code "55") (name "/pin7") (class "Default")
      (node (ref "C8") (pin "1") (pinfunction "1_1") (pintype "passive"))
      (node (ref "R1") (pin "1") (pinfunction "1_1") (pintype "passive"))
      (node (ref "X16") (pin "6") (pinfunction "6_6") (pintype "passive"))
      (node (ref "mcu") (pin "7") (pinfunction "NRST_7") (pintype "passive"))
    )
    (net (code "56") (name "/pin8") (class "Default")
      (node (ref "mcu") (pin "8") (pinfunction "PC0_8") (pintype "passive"))
      (node (ref "touch panel") (pin "6") (pinfunction "6_6") (pintype "passive"))
    )
    (net (code "57") (name "/pin9") (class "Default")
      (node (ref "mcu") (pin "9") (pinfunction "PC1_9") (pintype "passive"))
      (node (ref "touch panel") (pin "5") (pinfunction "5_5") (pintype "passive"))
    )
    (net (code "58") (name "/pin10") (class "Default")
      (node (ref "mcu") (pin "10") (pinfunction "PC2_10") (pintype "passive"))
      (node (ref "touch panel") (pin "4") (pinfunction "4_4") (pintype "passive"))
    )
    (net (code "59") (name "/pin11") (class "Default")
      (node (ref "mcu") (pin "11") (pinfunction "PC3_11") (pintype "passive"))
      (node (ref "touch panel") (pin "3") (pinfunction "3_3") (pintype "passive"))
    )
    (net (code "60") (name "/pin14") (class "Default")
      (node (ref "header") (pin "17") (pinfunction "17_17") (pintype "passive"))
      (node (ref "mcu") (pin "14") (pinfunction "PA0_14") (pintype "passive"))
    )
    (net (code "61") (name "/pin15") (class "Default")
      (node (ref "header") (pin "18") (pinfunction "18_18") (pintype "passive"))
      (node (ref "mcu") (pin "15") (pinfunction "PA1_15") (pintype "passive"))
    )
    (net (code "62") (name "/pin16") (class "Default")
      (node (ref "header") (pin "15") (pinfunction "15_15") (pintype "passive"))
      (node (ref "mcu") (pin "16") (pinfunction "PA2_16") (pintype "passive"))
    )
    (net (code "63") (name "/pin17") (class "Default")
      (node (ref "header") (pin "16") (pinfunction "16_16") (pintype "passive"))
      (node (ref "mcu") (pin "17") (pinfunction "PA3_17") (pintype "passive"))
    )
    (net (code "64") (name "/pin20") (class "Default")
      (node (ref "header") (pin "13") (pinfunction "13_13") (pintype "passive"))
      (node (ref "mcu") (pin "20") (pinfunction "PA4_20") (pintype "passive"))
    )
    (net (code "65") (name "/pin21") (class "Default")
      (node (ref "header") (pin "14") (pinfunction "14_14") (pintype "passive"))
      (node (ref "mcu") (pin "21") (pinfunction "PA5_21") (pintype "passive"))
    )
    (net (code "66") (name "/pin22") (class "Default")
      (node (ref "header") (pin "11") (pinfunction "11_11") (pintype "passive"))
      (node (ref "mcu") (pin "22") (pinfunction "PA6_22") (pintype "passive"))
    )
    (net (code "67") (name "/pin23") (class "Default")
      (node (ref "header") (pin "12") (pinfunction "12_12") (pintype "passive"))
      (node (ref "mcu") (pin "23") (pinfunction "PA7_23") (pintype "passive"))
    )
    (net (code "68") (name "/pin24") (class "Default")
      (node (ref "R6") (pin "1") (pinfunction "1_1") (pintype "passive"))
      (node (ref "mcu") (pin "24") (pinfunction "PC4_24") (pintype "passive"))
    )
    (net (code "69") (name "/pin26") (class "Default")
      (node (ref "R9") (pin "1") (pinfunction "1_1") (pintype "passive"))
      (node (ref "mcu") (pin "26") (pinfunction "PB0_26") (pintype "passive"))
    )
    (net (code "70") (name "/pin27") (class "Default")
      (node (ref "R8") (pin "1") (pinfunction "1_1") (pintype "passive"))
      (node (ref "mcu") (pin "27") (pinfunction "PB1_27") (pintype "passive"))
    )
    (net (code "71") (name "/pin28") (class "Default")
      (node (ref "C6") (pin "1") (pinfunction "1_1") (pintype "passive"))
      (node (ref "U5") (pin "11") (pinfunction "OUT_6_11") (pintype "passive"))
      (node (ref "mcu") (pin "28") (pinfunction "PB2_28") (pintype "passive"))
    )
    (net (code "72") (name "/pin29") (class "Default")
      (node (ref "C5") (pin "1") (pinfunction "1_1") (pintype "passive"))
      (node (ref "U5") (pin "10") (pinfunction "OUT_7_10") (pintype "passive"))
      (node (ref "mcu") (pin "29") (pinfunction "PB10_29") (pintype "passive"))
    )
    (net (code "73") (name "/pin30") (class "Default")
      (node (ref "C4") (pin "2") (pinfunction "2_2") (pintype "passive"))
      (node (ref "mcu") (pin "30") (pinfunction "VCAP_1_30") (pintype "passive"))
    )
    (net (code "74") (name "/pin31") (class "Default")
      (node (ref "C4") (pin "1") (pinfunction "1_1") (pintype "passive"))
      (node (ref "mcu") (pin "31") (pinfunction "VSS_2_31") (pintype "passive"))
    )
    (net (code "75") (name "/pin33") (class "Default")
      (node (ref "R5") (pin "2") (pinfunction "2_2") (pintype "passive"))
      (node (ref "mcu") (pin "33") (pinfunction "PB12_33") (pintype "passive"))
    )
    (net (code "76") (name "/pin34") (class "Default")
      (node (ref "R4") (pin "2") (pinfunction "2_2") (pintype "passive"))
      (node (ref "mcu") (pin "34") (pinfunction "PB13_34") (pintype "passive"))
    )
    (net (code "77") (name "/pin35") (class "Default")
      (node (ref "R3") (pin "2") (pinfunction "2_2") (pintype "passive"))
      (node (ref "mcu") (pin "35") (pinfunction "PB14_35") (pintype "passive"))
    )
    (net (code "78") (name "/pin36") (class "Default")
      (node (ref "C3") (pin "1") (pinfunction "1_1") (pintype "passive"))
      (node (ref "U5") (pin "9") (pinfunction "COMMON_FREE_WHEELING_DIODES_9") (pintype "passive"))
      (node (ref "mcu") (pin "36") (pinfunction "PB15_36") (pintype "passive"))
    )
    (net (code "79") (name "/pin37") (class "Default")
      (node (ref "X7") (pin "2") (pinfunction "2_2") (pintype "passive"))
      (node (ref "mcu") (pin "37") (pinfunction "PC6_37") (pintype "passive"))
    )
    (net (code "80") (name "/pin38") (class "Default")
      (node (ref "X7") (pin "3") (pinfunction "3_3") (pintype "passive"))
      (node (ref "mcu") (pin "38") (pinfunction "PC7_38") (pintype "passive"))
    )
    (net (code "81") (name "/pin39") (class "Default")
      (node (ref "C2") (pin "1") (pinfunction "1_1") (pintype "passive"))
      (node (ref "U5") (pin "3") (pinfunction "IN_3_3") (pintype "passive"))
      (node (ref "mcu") (pin "39") (pinfunction "PC8_39") (pintype "passive"))
    )
    (net (code "82") (name "/pin40") (class "Default")
      (node (ref "C1") (pin "1") (pinfunction "1_1") (pintype "passive"))
      (node (ref "U5") (pin "7") (pinfunction "IN_7_7") (pintype "passive"))
      (node (ref "mcu") (pin "40") (pinfunction "PC9_40") (pintype "passive"))
    )
    (net (code "83") (name "/pin41") (class "Default")
      (node (ref "header") (pin "4") (pinfunction "4_4") (pintype "passive"))
      (node (ref "mcu") (pin "41") (pinfunction "PA8_41") (pintype "passive"))
    )
    (net (code "84") (name "/pin42") (class "Default")
      (node (ref "header") (pin "3") (pinfunction "3_3") (pintype "passive"))
      (node (ref "mcu") (pin "42") (pinfunction "PA9_42") (pintype "passive"))
    )
    (net (code "85") (name "/pin43") (class "Default")
      (node (ref "header") (pin "6") (pinfunction "6_6") (pintype "passive"))
      (node (ref "mcu") (pin "43") (pinfunction "PA10_43") (pintype "passive"))
    )
    (net (code "86") (name "/pin44") (class "Default")
      (node (ref "header") (pin "5") (pinfunction "5_5") (pintype "passive"))
      (node (ref "mcu") (pin "44") (pinfunction "PA11_44") (pintype "passive"))
    )
    (net (code "87") (name "/pin45") (class "Default")
      (node (ref "header") (pin "8") (pinfunction "8_8") (pintype "passive"))
      (node (ref "mcu") (pin "45") (pinfunction "PA12_45") (pintype "passive"))
    )
    (net (code "88") (name "/pin46") (class "Default")
      (node (ref "X16") (pin "5") (pinfunction "5_5") (pintype "passive"))
      (node (ref "X9") (pin "1") (pinfunction "1_1") (pintype "passive"))
      (node (ref "mcu") (pin "46") (pinfunction "PA13_46") (pintype "passive"))
    )
    (net (code "89") (name "/pin48") (class "Default")
      (node (ref "R1") (pin "2") (pinfunction "2_2") (pintype "passive"))
      (node (ref "X12") (pin "1") (pinfunction "1_1") (pintype "passive"))
      (node (ref "mcu") (pin "1") (pinfunction "VBAT_1") (pintype "passive"))
      (node (ref "mcu") (pin "13") (pinfunction "VDDA/VREF+_13") (pintype "passive"))
      (node (ref "mcu") (pin "19") (pinfunction "VDD_1_19") (pintype "passive"))
      (node (ref "mcu") (pin "32") (pinfunction "VDD_2_32") (pintype "passive"))
      (node (ref "mcu") (pin "48") (pinfunction "VDD_3_48") (pintype "passive"))
      (node (ref "mcu") (pin "64") (pinfunction "VDD_4_64") (pintype "passive"))
    )
    (net (code "90") (name "/pin49") (class "Default")
      (node (ref "X10") (pin "1") (pinfunction "1_1") (pintype "passive"))
      (node (ref "X16") (pin "3") (pinfunction "3_3") (pintype "passive"))
      (node (ref "mcu") (pin "49") (pinfunction "PA14_49") (pintype "passive"))
    )
    (net (code "91") (name "/pin50") (class "Default")
      (node (ref "header") (pin "9") (pinfunction "9_9") (pintype "passive"))
      (node (ref "mcu") (pin "50") (pinfunction "PA15_50") (pintype "passive"))
    )
    (net (code "92") (name "/pin51") (class "Default")
      (node (ref "R16") (pin "2") (pinfunction "2_2") (pintype "passive"))
      (node (ref "mcu") (pin "51") (pinfunction "PC10_51") (pintype "passive"))
    )
    (net (code "93") (name "/pin52") (class "Default")
      (node (ref "R17") (pin "2") (pinfunction "2_2") (pintype "passive"))
      (node (ref "mcu") (pin "52") (pinfunction "PC11_52") (pintype "passive"))
    )
    (net (code "94") (name "/pin53") (class "Default")
      (node (ref "C9") (pin "1") (pinfunction "1_1") (pintype "passive"))
      (node (ref "U5") (pin "6") (pinfunction "IN_6_6") (pintype "passive"))
      (node (ref "mcu") (pin "53") (pinfunction "PC12_53") (pintype "passive"))
    )
    (net (code "95") (name "/pin54") (class "Default")
      (node (ref "C10") (pin "1") (pinfunction "1_1") (pintype "passive"))
      (node (ref "U5") (pin "5") (pinfunction "IN_5_5") (pintype "passive"))
      (node (ref "mcu") (pin "54") (pinfunction "PD2_54") (pintype "passive"))
    )
    (net (code "96") (name "/pin55") (class "Default")
      (node (ref "X11") (pin "1") (pinfunction "1_1") (pintype "passive"))
      (node (ref "X16") (pin "2") (pinfunction "2_2") (pintype "passive"))
      (node (ref "mcu") (pin "55") (pinfunction "PB3_55") (pintype "passive"))
    )
    (net (code "97") (name "/pin56") (class "Default")
      (node (ref "header") (pin "19") (pinfunction "19_19") (pintype "passive"))
      (node (ref "mcu") (pin "56") (pinfunction "PB4_56") (pintype "passive"))
    )
    (net (code "98") (name "/pin57") (class "Default")
      (node (ref "header") (pin "20") (pinfunction "20_20") (pintype "passive"))
      (node (ref "mcu") (pin "57") (pinfunction "PB5_57") (pintype "passive"))
    )
    (net (code "99") (name "/pin58") (class "Default")
      (node (ref "header") (pin "21") (pinfunction "21_21") (pintype "passive"))
      (node (ref "mcu") (pin "58") (pinfunction "PB6_58") (pintype "passive"))
    )
    (net (code "100") (name "/pin59") (class "Default")
      (node (ref "header") (pin "22") (pinfunction "22_22") (pintype "passive"))
      (node (ref "mcu") (pin "59") (pinfunction "PB7_59") (pintype "passive"))
    )
    (net (code "101") (name "/pin60") (class "Default")
      (node (ref "R2") (pin "2") (pinfunction "2_2") (pintype "passive"))
      (node (ref "mcu") (pin "60") (pinfunction "BOOT0_60") (pintype "passive"))
    )
    (net (code "102") (name "/pin61") (class "Default")
      (node (ref "C11") (pin "1") (pinfunction "1_1") (pintype "passive"))
      (node (ref "U5") (pin "4") (pinfunction "IN_4_4") (pintype "passive"))
      (node (ref "mcu") (pin "61") (pinfunction "PB8_61") (pintype "passive"))
    )
    (net (code "103") (name "/pin62") (class "Default")
      (node (ref "R15") (pin "2") (pinfunction "2_2") (pintype "passive"))
      (node (ref "mcu") (pin "62") (pinfunction "PB9_62") (pintype "passive"))
    )
    (net (code "104") (name "/smdLed1") (class "Default")
      (node (ref "D3") (pin "2") (pinfunction "A_2") (pintype "passive"))
      (node (ref "X11") (pin "2") (pinfunction "2_2") (pintype "passive"))
    )
    (net (code "105") (name "GND") (class "Default")
      (node (ref "C12") (pin "2") (pinfunction "-_2") (pintype "passive"))
      (node (ref "C13") (pin "1") (pinfunction "+_1") (pintype "passive"))
      (node (ref "C15") (pin "1") (pinfunction "+_1") (pintype "passive"))
      (node (ref "C16") (pin "1") (pinfunction "+_1") (pintype "passive"))
      (node (ref "C17") (pin "2") (pinfunction "2_2") (pintype "passive"))
      (node (ref "C18") (pin "2") (pinfunction "-_2") (pintype "passive"))
      (node (ref "C20") (pin "2") (pinfunction "2_2") (pintype "passive"))
      (node (ref "C3") (pin "2") (pinfunction "2_2") (pintype "passive"))
      (node (ref "C34") (pin "2") (pinfunction "-_2") (pintype "passive"))
      (node (ref "C5") (pin "2") (pinfunction "2_2") (pintype "passive"))
      (node (ref "C6") (pin "2") (pinfunction "2_2") (pintype "passive"))
      (node (ref "C7") (pin "2") (pinfunction "2_2") (pintype "passive"))
      (node (ref "C8") (pin "2") (pinfunction "2_2") (pintype "passive"))
      (node (ref "Q1") (pin "2") (pinfunction "E_2") (pintype "passive"))
      (node (ref "Q2") (pin "2") (pinfunction "E_2") (pintype "passive"))
      (node (ref "Q3") (pin "2") (pinfunction "E_2") (pintype "passive"))
      (node (ref "Q4") (pin "2") (pinfunction "E_2") (pintype "passive"))
      (node (ref "Q5") (pin "2") (pinfunction "E_2") (pintype "passive"))
      (node (ref "Q6") (pin "2") (pinfunction "E_2") (pintype "passive"))
      (node (ref "Q7") (pin "3") (pinfunction "SOURCE_3") (pintype "passive"))
      (node (ref "Q8") (pin "3") (pinfunction "SOURCE_3") (pintype "passive"))
      (node (ref "Q9") (pin "2") (pinfunction "E_2") (pintype "passive"))
      (node (ref "R2") (pin "1") (pinfunction "1_1") (pintype "passive"))
      (node (ref "R30") (pin "1") (pinfunction "1_1") (pintype "passive"))
      (node (ref "U2") (pin "1") (pinfunction "GROUND/ADJUST_1") (pintype "passive"))
      (node (ref "U3") (pin "1") (pinfunction "GROUND/ADJUST_1") (pintype "passive"))
      (node (ref "U4") (pin "1") (pinfunction "GROUND/ADJUST_1") (pintype "passive"))
      (node (ref "U5") (pin "13") (pinfunction "OUT_4_13") (pintype "passive"))
      (node (ref "U5") (pin "14") (pinfunction "OUT_3_14") (pintype "passive"))
      (node (ref "U6") (pin "2") (pinfunction "CATHODE_2") (pintype "passive"))
      (node (ref "U7") (pin "2") (pinfunction "CATHODE_2") (pintype "passive"))
      (node (ref "U8") (pin "2") (pinfunction "CATHODE_2") (pintype "passive"))
      (node (ref "X16") (pin "4") (pinfunction "4_4") (pintype "passive"))
      (node (ref "X3") (pin "2") (pinfunction "2_2") (pintype "passive"))
      (node (ref "X7") (pin "7") (pinfunction "7_7") (pintype "passive"))
      (node (ref "mcu") (pin "12") (pinfunction "VSSA/VREF-_12") (pintype "passive"))
      (node (ref "mcu") (pin "18") (pinfunction "VSS_1_18") (pintype "passive"))
      (node (ref "mcu") (pin "47") (pinfunction "VSS_3_47") (pintype "passive"))
      (node (ref "mcu") (pin "63") (pinfunction "VSS_4_63") (pintype "passive"))
      (node (ref "touch panel") (pin "8") (pinfunction "8_8") (pintype "passive"))
    )
    (net (code "106") (name "unconnected-(P3-Pad1)") (class "Default")
      (node (ref "P3") (pin "1") (pinfunction "1_1") (pintype "passive"))
    )
    (net (code "107") (name "unconnected-(P3-Pad2)") (class "Default")
      (node (ref "P3") (pin "2") (pinfunction "2_2") (pintype "passive"))
    )
    (net (code "108") (name "unconnected-(P3-Pad3)") (class "Default")
      (node (ref "P3") (pin "3") (pinfunction "3_3") (pintype "passive"))
    )
    (net (code "109") (name "unconnected-(P3-Pad4)") (class "Default")
      (node (ref "P3") (pin "4") (pinfunction "4_4") (pintype "passive"))
    )
    (net (code "110") (name "unconnected-(P3-Pad5)") (class "Default")
      (node (ref "P3") (pin "5") (pinfunction "5_5") (pintype "passive"))
    )
    (net (code "111") (name "unconnected-(P3-Pad6)") (class "Default")
      (node (ref "P3") (pin "6") (pinfunction "6_6") (pintype "passive"))
    )
    (net (code "112") (name "unconnected-(P3-Pad7)") (class "Default")
      (node (ref "P3") (pin "7") (pinfunction "7_7") (pintype "passive"))
    )
    (net (code "113") (name "unconnected-(P3-Pad8)") (class "Default")
      (node (ref "P3") (pin "8") (pinfunction "8_8") (pintype "passive"))
    )
    (net (code "114") (name "unconnected-(U2-TAB-Pad4)") (class "Default")
      (node (ref "U2") (pin "4") (pinfunction "TAB_4") (pintype "passive"))
    )
    (net (code "115") (name "unconnected-(U3-TAB-Pad4)") (class "Default")
      (node (ref "U3") (pin "4") (pinfunction "TAB_4") (pintype "passive"))
    )
    (net (code "116") (name "unconnected-(U4-VOUT-Pad2)") (class "Default")
      (node (ref "U4") (pin "2") (pinfunction "VOUT_2") (pintype "passive"))
    )
    (net (code "117") (name "unconnected-(U5-GND-Pad8)") (class "Default")
      (node (ref "U5") (pin "8") (pinfunction "GND_8") (pintype "passive"))
    )
    (net (code "118") (name "unconnected-(U5-OUT_1-Pad16)") (class "Default")
      (node (ref "U5") (pin "16") (pinfunction "OUT_1_16") (pintype "passive"))
    )
    (net (code "119") (name "unconnected-(U5-OUT_2-Pad15)") (class "Default")
      (node (ref "U5") (pin "15") (pinfunction "OUT_2_15") (pintype "passive"))
    )
    (net (code "120") (name "unconnected-(U6-NC-Pad5)") (class "Default")
      (node (ref "U6") (pin "5") (pinfunction "NC_5") (pintype "passive"))
    )
    (net (code "121") (name "unconnected-(U6-N{slash}C-Pad3)") (class "Default")
      (node (ref "U6") (pin "3") (pinfunction "N/C_3") (pintype "passive"))
    )
    (net (code "122") (name "unconnected-(U7-NC-Pad5)") (class "Default")
      (node (ref "U7") (pin "5") (pinfunction "NC_5") (pintype "passive"))
    )
    (net (code "123") (name "unconnected-(U7-N{slash}C-Pad3)") (class "Default")
      (node (ref "U7") (pin "3") (pinfunction "N/C_3") (pintype "passive"))
    )
    (net (code "124") (name "unconnected-(U8-NC-Pad5)") (class "Default")
      (node (ref "U8") (pin "5") (pinfunction "NC_5") (pintype "passive"))
    )
    (net (code "125") (name "unconnected-(U8-N{slash}C-Pad3)") (class "Default")
      (node (ref "U8") (pin "3") (pinfunction "N/C_3") (pintype "passive"))
    )
    (net (code "126") (name "unconnected-(X3-Pad1)") (class "Default")
      (node (ref "X3") (pin "1") (pinfunction "1_1") (pintype "passive+no_connect"))
    )
    (net (code "127") (name "unconnected-(X7-Pad4)") (class "Default")
      (node (ref "X7") (pin "4") (pinfunction "4_4") (pintype "passive"))
    )
    (net (code "128") (name "unconnected-(X7-Pad5)") (class "Default")
      (node (ref "X7") (pin "5") (pinfunction "5_5") (pintype "passive"))
    )
    (net (code "129") (name "unconnected-(header-Pad23)") (class "Default")
      (node (ref "header") (pin "23") (pinfunction "23_23") (pintype "passive"))
    )
    (net (code "130") (name "unconnected-(header-Pad24)") (class "Default")
      (node (ref "header") (pin "24") (pinfunction "24_24") (pintype "passive"))
    )
    (net (code "131") (name "unconnected-(header-Pad25)") (class "Default")
      (node (ref "header") (pin "25") (pinfunction "25_25") (pintype "passive"))
    )
    (net (code "132") (name "unconnected-(header-Pad26)") (class "Default")
      (node (ref "header") (pin "26") (pinfunction "26_26") (pintype "passive"))
    )
    (net (code "133") (name "unconnected-(header-Pad27)") (class "Default")
      (node (ref "header") (pin "27") (pinfunction "27_27") (pintype "passive"))
    )
    (net (code "134") (name "unconnected-(header-Pad28)") (class "Default")
      (node (ref "header") (pin "28") (pinfunction "28_28") (pintype "passive"))
    )
    (net (code "135") (name "unconnected-(header-Pad29)") (class "Default")
      (node (ref "header") (pin "29") (pinfunction "29_29") (pintype "passive"))
    )
    (net (code "136") (name "unconnected-(header-Pad31)") (class "Default")
      (node (ref "header") (pin "31") (pinfunction "31_31") (pintype "passive"))
    )
    (net (code "137") (name "unconnected-(header-Pad32)") (class "Default")
      (node (ref "header") (pin "32") (pinfunction "32_32") (pintype "passive"))
    )
    (net (code "138") (name "unconnected-(header-Pad33)") (class "Default")
      (node (ref "header") (pin "33") (pinfunction "33_33") (pintype "passive"))
    )
    (net (code "139") (name "unconnected-(header-Pad34)") (class "Default")
      (node (ref "header") (pin "34") (pinfunction "34_34") (pintype "passive"))
    )
    (net (code "140") (name "unconnected-(header-Pad35)") (class "Default")
      (node (ref "header") (pin "35") (pinfunction "35_35") (pintype "passive"))
    )
    (net (code "141") (name "unconnected-(header-Pad36)") (class "Default")
      (node (ref "header") (pin "36") (pinfunction "36_36") (pintype "passive"))
    )
    (net (code "142") (name "unconnected-(mcu-PC14-OSC32_IN-Pad3)") (class "Default")
      (node (ref "mcu") (pin "3") (pinfunction "PC14-OSC32_IN_3") (pintype "passive"))
    )
    (net (code "143") (name "unconnected-(mcu-PC15-OSC32_OUT-Pad4)") (class "Default")
      (node (ref "mcu") (pin "4") (pinfunction "PC15-OSC32_OUT_4") (pintype "passive"))
    )
    (net (code "144") (name "unconnected-(touch panel-PadMH1)") (class "Default")
      (node (ref "touch panel") (pin "MH1") (pinfunction "MH1_MH1") (pintype "passive"))
    )
    (net (code "145") (name "unconnected-(touch panel-PadMH2)") (class "Default")
      (node (ref "touch panel") (pin "MH2") (pinfunction "MH2_MH2") (pintype "passive"))
    )
  )
)
